# Becca_Sap_Flow_Sensor_MOD3.net
KiCad netlist of a schematic drawn in EAGLE
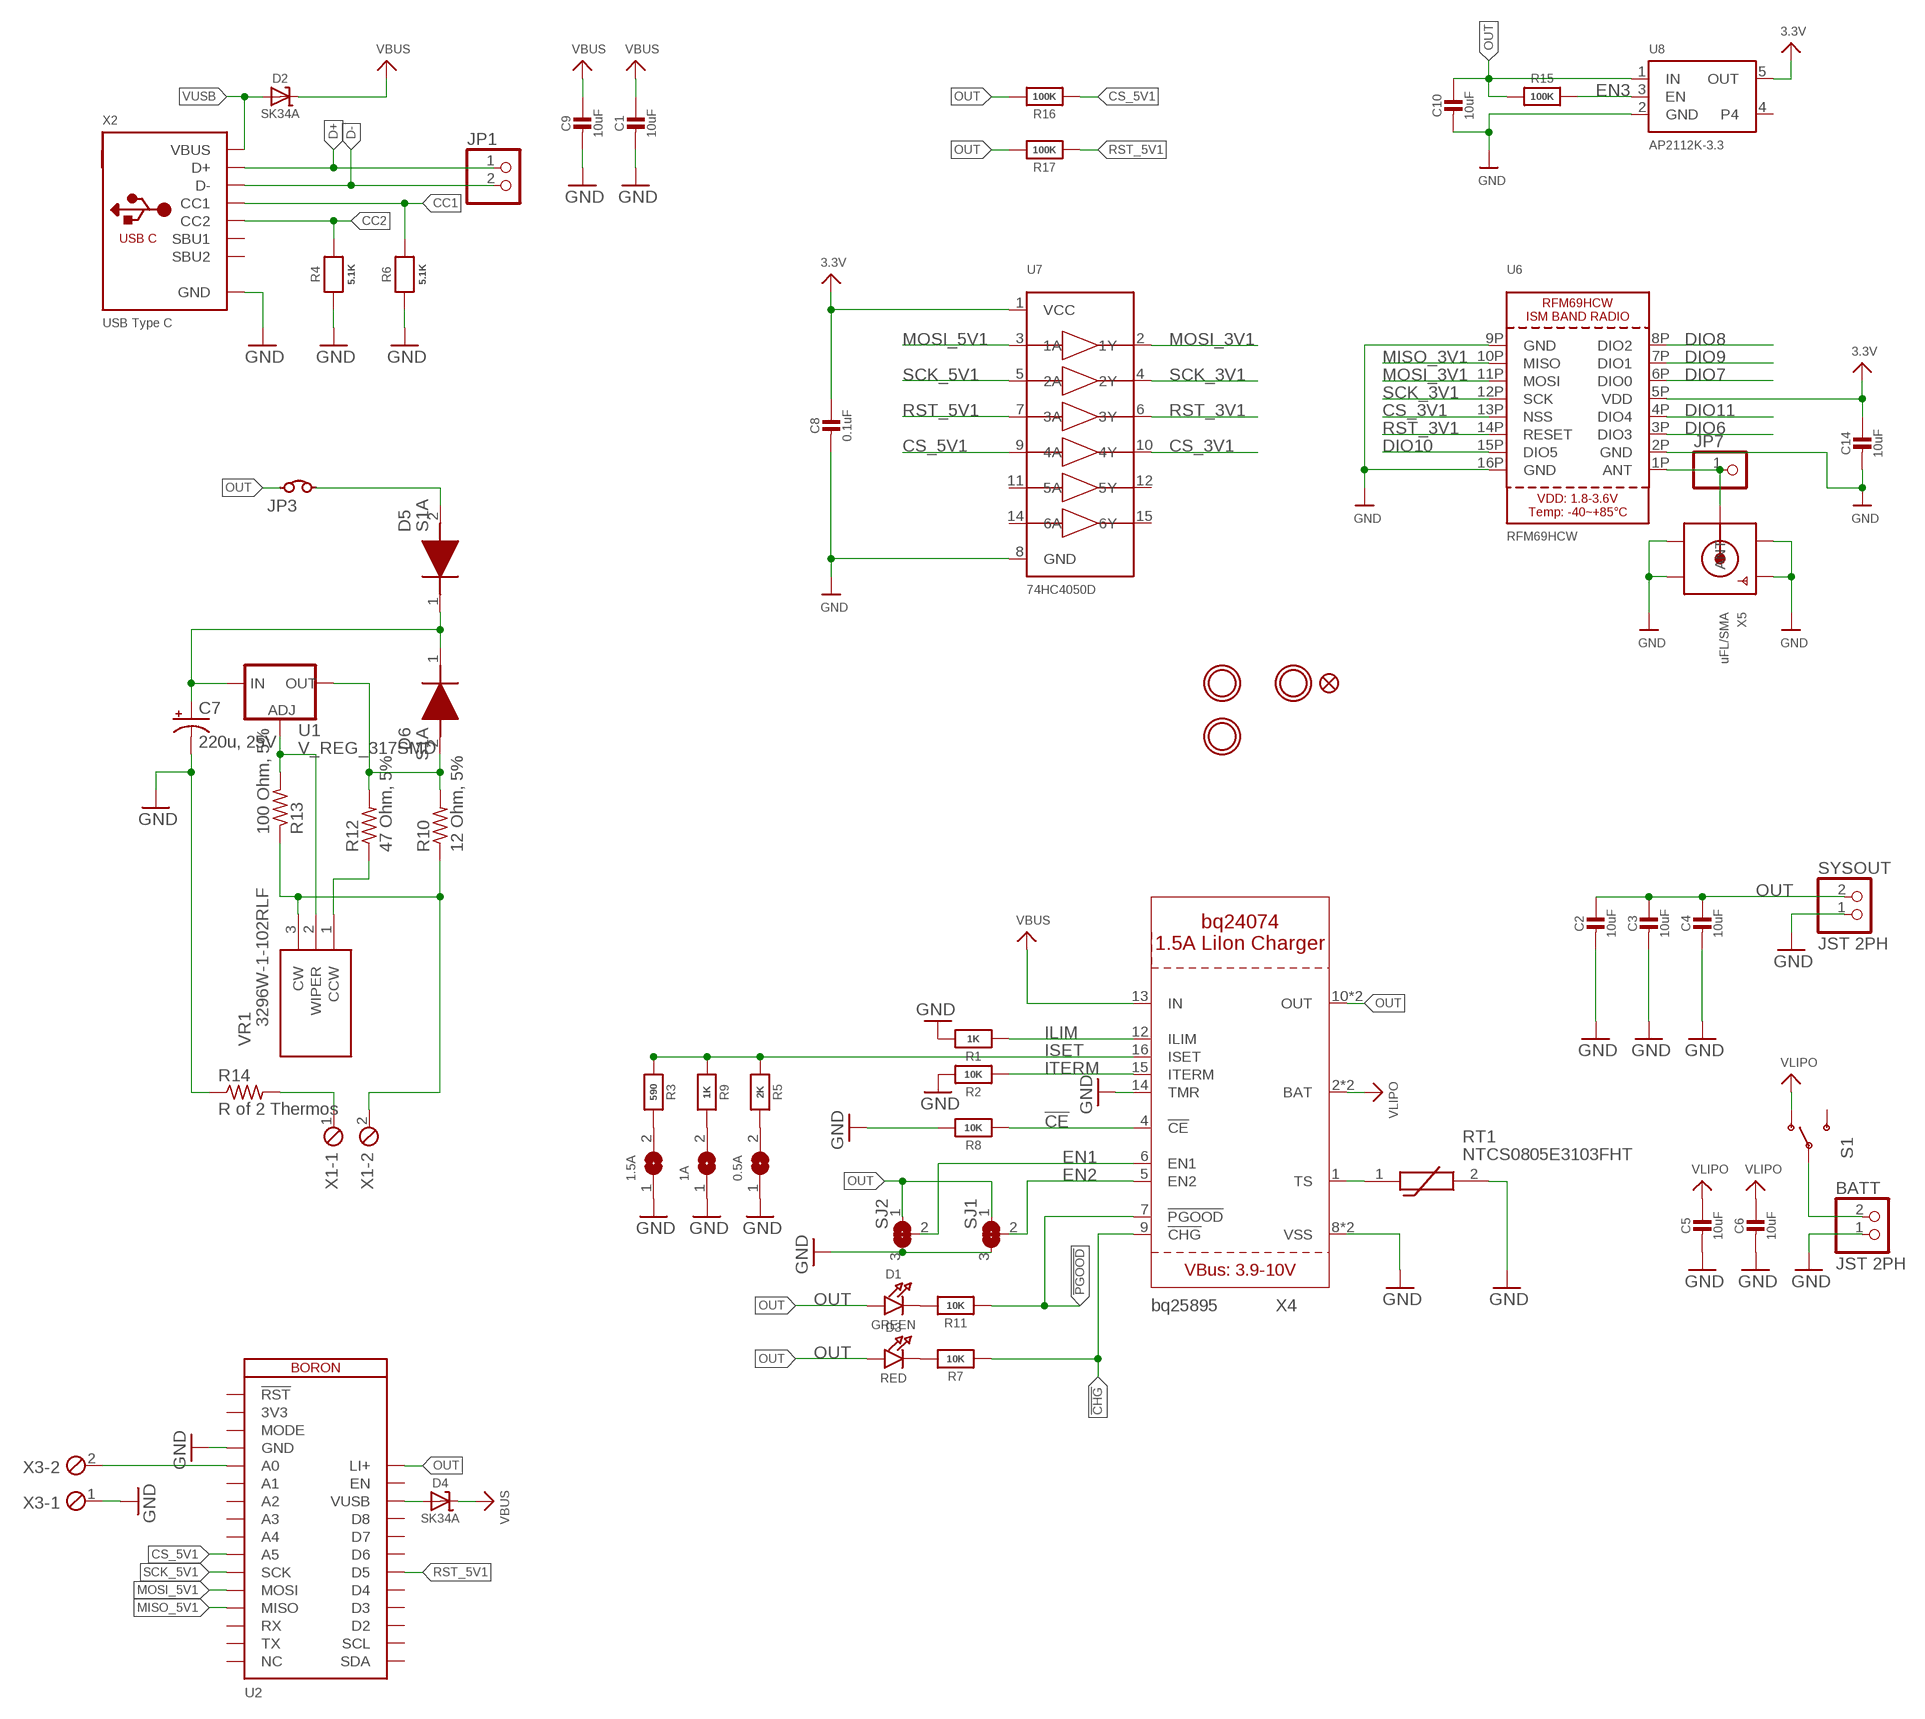
[diagram p0: schematic, sheet 1]

(export (version "E")
  (design (tool "Eeschema 10.0.6"))
  (components
    (comp (ref "0.5A")
      (value "SOLDERJUMPER")
      (footprint "eagle-import:SOLDERJUMPER_ARROW_NOPASTE")
      (libsource (lib "eagle-import") (part "SOLDERJUMPER"))
    )
    (comp (ref "1.5A")
      (value "SOLDERJUMPER")
      (footprint "eagle-import:SOLDERJUMPER_ARROW_NOPASTE")
      (libsource (lib "eagle-import") (part "SOLDERJUMPER"))
    )
    (comp (ref "1A")
      (value "SOLDERJUMPERCLOSED")
      (footprint "eagle-import:SOLDERJUMPER_CLOSEDWIRE")
      (libsource (lib "eagle-import") (part "SOLDERJUMPERCLOSED"))
    )
    (comp (ref "BATT")
      (value "JST 2PH")
      (footprint "eagle-import:JST-PH-2-THM-RA")
      (libsource (lib "eagle-import") (part "JST_2PIN-THM-RA"))
    )
    (comp (ref "C1")
      (value "10uF")
      (footprint "eagle-import:0805-NO")
      (libsource (lib "eagle-import") (part "CAP_CERAMIC0805-NOOUTLINE"))
    )
    (comp (ref "C2")
      (value "10uF")
      (footprint "eagle-import:0805-NO")
      (libsource (lib "eagle-import") (part "CAP_CERAMIC0805-NOOUTLINE"))
    )
    (comp (ref "C3")
      (value "10uF")
      (footprint "eagle-import:0805-NO")
      (libsource (lib "eagle-import") (part "CAP_CERAMIC0805-NOOUTLINE"))
    )
    (comp (ref "C4")
      (value "10uF")
      (footprint "eagle-import:0805-NO")
      (libsource (lib "eagle-import") (part "CAP_CERAMIC0805-NOOUTLINE"))
    )
    (comp (ref "C5")
      (value "10uF")
      (footprint "eagle-import:0805-NO")
      (libsource (lib "eagle-import") (part "CAP_CERAMIC0805-NOOUTLINE"))
    )
    (comp (ref "C6")
      (value "10uF")
      (footprint "eagle-import:0805-NO")
      (libsource (lib "eagle-import") (part "CAP_CERAMIC0805-NOOUTLINE"))
    )
    (comp (ref "C7")
      (value "220u, 25V")
      (footprint "eagle-import:PANASONIC_C")
      (libsource (lib "eagle-import") (part "CPOL-USC"))
    )
    (comp (ref "C8")
      (value "0.1uF")
      (footprint "eagle-import:0805-NO")
      (libsource (lib "eagle-import") (part "CAP_CERAMIC0805-NOOUTLINE"))
    )
    (comp (ref "C9")
      (value "10uF")
      (footprint "eagle-import:0805-NO")
      (libsource (lib "eagle-import") (part "CAP_CERAMIC0805-NOOUTLINE"))
    )
    (comp (ref "C10")
      (value "10uF")
      (footprint "eagle-import:0805-NO")
      (libsource (lib "eagle-import") (part "CAP_CERAMIC0805-NOOUTLINE"))
    )
    (comp (ref "C14")
      (value "10uF")
      (footprint "eagle-import:0805-NO")
      (libsource (lib "eagle-import") (part "CAP_CERAMIC0805-NOOUTLINE"))
    )
    (comp (ref "D1")
      (value "GREEN")
      (footprint "eagle-import:CHIPLED_0603")
      (libsource (lib "eagle-import") (part "LED0603"))
    )
    (comp (ref "D2")
      (value "SK34A")
      (footprint "eagle-import:SMADIODE")
      (libsource (lib "eagle-import") (part "DIODE-SCHOTTKYSMA"))
    )
    (comp (ref "D3")
      (value "RED")
      (footprint "eagle-import:CHIPLED_0603")
      (libsource (lib "eagle-import") (part "LED0603"))
    )
    (comp (ref "D4")
      (value "SK34A")
      (footprint "eagle-import:SMADIODE")
      (libsource (lib "eagle-import") (part "DIODE-SCHOTTKYSMA"))
    )
    (comp (ref "D5")
      (value "S1A")
      (footprint "eagle-import:DIOM5027X250N")
      (fields (field (name "MOUSER_PART_NUMBER") "637-S1A"))
      (libsource (lib "eagle-import") (part "S1A"))
    )
    (comp (ref "D6")
      (value "S1A")
      (footprint "eagle-import:DIOM5027X250N")
      (fields (field (name "MOUSER_PART_NUMBER") "637-S1A"))
      (libsource (lib "eagle-import") (part "S1A"))
    )
    (comp (ref "FID2")
      (value "FIDUCIAL_1MM")
      (footprint "eagle-import:FIDUCIAL_1MM")
      (libsource (lib "eagle-import") (part "FIDUCIAL_1MM"))
    )
    (comp (ref "JP1")
      (value "HEADER-1X2ROUND")
      (footprint "eagle-import:1X02_ROUND")
      (libsource (lib "eagle-import") (part "HEADER-1X2ROUND"))
    )
    (comp (ref "JP3")
      (value "JUMPER")
      (footprint "eagle-import:HDR2X1")
      (libsource (lib "eagle-import") (part "JUMPER"))
    )
    (comp (ref "JP7")
      (value "HEADER-1X1ROUND")
      (footprint "eagle-import:1X01_ROUND")
      (libsource (lib "eagle-import") (part "HEADER-1X1ROUND"))
    )
    (comp (ref "R1")
      (value "1K")
      (footprint "eagle-import:0603-NO")
      (libsource (lib "eagle-import") (part "RESISTOR_0603_NOOUT"))
    )
    (comp (ref "R2")
      (value "10K")
      (footprint "eagle-import:0603-NO")
      (libsource (lib "eagle-import") (part "RESISTOR_0603_NOOUT"))
    )
    (comp (ref "R3")
      (value "590")
      (footprint "eagle-import:0603-NO")
      (libsource (lib "eagle-import") (part "RESISTOR_0603_NOOUT"))
    )
    (comp (ref "R4")
      (value "5.1K")
      (footprint "eagle-import:0603-NO")
      (libsource (lib "eagle-import") (part "RESISTOR_0603_NOOUT"))
    )
    (comp (ref "R5")
      (value "2K")
      (footprint "eagle-import:0603-NO")
      (libsource (lib "eagle-import") (part "RESISTOR_0603_NOOUT"))
    )
    (comp (ref "R6")
      (value "5.1K")
      (footprint "eagle-import:0603-NO")
      (libsource (lib "eagle-import") (part "RESISTOR_0603_NOOUT"))
    )
    (comp (ref "R7")
      (value "10K")
      (footprint "eagle-import:0603-NO")
      (libsource (lib "eagle-import") (part "RESISTOR_0603_NOOUT"))
    )
    (comp (ref "R8")
      (value "10K")
      (footprint "eagle-import:0603-NO")
      (libsource (lib "eagle-import") (part "RESISTOR_0603_NOOUT"))
    )
    (comp (ref "R9")
      (value "1K")
      (footprint "eagle-import:0603-NO")
      (libsource (lib "eagle-import") (part "RESISTOR_0603_NOOUT"))
    )
    (comp (ref "R10")
      (value "12 Ohm, 5%")
      (footprint "eagle-import:R0805")
      (libsource (lib "eagle-import") (part "R-US_R0805"))
    )
    (comp (ref "R11")
      (value "10K")
      (footprint "eagle-import:0603-NO")
      (libsource (lib "eagle-import") (part "RESISTOR_0603_NOOUT"))
    )
    (comp (ref "R12")
      (value "47 Ohm, 5%")
      (footprint "eagle-import:R0805")
      (libsource (lib "eagle-import") (part "R-US_R0805"))
    )
    (comp (ref "R13")
      (value "100 Ohm, 5%")
      (footprint "eagle-import:R0805")
      (libsource (lib "eagle-import") (part "R-US_R0805"))
    )
    (comp (ref "R14")
      (value "R of 2 Thermos")
      (footprint "eagle-import:R0805")
      (libsource (lib "eagle-import") (part "R-US_R0805"))
    )
    (comp (ref "R15")
      (value "100K")
      (footprint "eagle-import:0805-NO")
      (libsource (lib "eagle-import") (part "RESISTOR0805_NOOUTLINE"))
    )
    (comp (ref "R16")
      (value "100K")
      (footprint "eagle-import:0805-NO")
      (libsource (lib "eagle-import") (part "RESISTOR0805_NOOUTLINE"))
    )
    (comp (ref "R17")
      (value "100K")
      (footprint "eagle-import:0805-NO")
      (libsource (lib "eagle-import") (part "RESISTOR0805_NOOUTLINE"))
    )
    (comp (ref "RT1")
      (value "NTCS0805E3103FHT")
      (footprint "eagle-import:THRMC2012X95N")
      (fields (field (name "MOUSER_PART_NUMBER") "594-NTCS0805E3103FHT"))
      (libsource (lib "eagle-import") (part "NTCS0805E3103FHT"))
    )
    (comp (ref "S1")
      (value "SWITCH-SPDTSMD")
      (footprint "eagle-import:SWITCH_SPDT_SMD")
      (libsource (lib "eagle-import") (part "SWITCH-SPDTSMD"))
    )
    (comp (ref "SJ1")
      (value "SOLDERJUMPER_2WAY")
      (footprint "eagle-import:SOLDERJUMPER_2WAY_OPEN_NOPASTE")
      (libsource (lib "eagle-import") (part "SOLDERJUMPER_2WAY"))
    )
    (comp (ref "SJ2")
      (value "SOLDERJUMPER_2WAY")
      (footprint "eagle-import:SOLDERJUMPER_2WAY_OPEN_NOPASTE")
      (libsource (lib "eagle-import") (part "SOLDERJUMPER_2WAY"))
    )
    (comp (ref "SYSOUT")
      (value "JST 2PH")
      (footprint "eagle-import:JST-PH-2-THM-RA")
      (libsource (lib "eagle-import") (part "JST_2PIN-THM-RA"))
    )
    (comp (ref "U$3")
      (value "MOUNTINGHOLE2.5")
      (footprint "eagle-import:MOUNTINGHOLE_2.5_PLATED")
      (libsource (lib "eagle-import") (part "MOUNTINGHOLE2.5"))
    )
    (comp (ref "U$4")
      (value "MOUNTINGHOLE2.5")
      (footprint "eagle-import:MOUNTINGHOLE_2.5_PLATED")
      (libsource (lib "eagle-import") (part "MOUNTINGHOLE2.5"))
    )
    (comp (ref "U$11")
      (value "MOUNTINGHOLE2.5")
      (footprint "eagle-import:MOUNTINGHOLE_2.5_PLATED")
      (libsource (lib "eagle-import") (part "MOUNTINGHOLE2.5"))
    )
    (comp (ref "U1")
      (value "V_REG_317SMD")
      (footprint "eagle-import:SOT223")
      (libsource (lib "eagle-import") (part "V_REG_317SMD"))
    )
    (comp (ref "U2")
      (value "BORON")
      (footprint "eagle-import:BORON")
      (libsource (lib "eagle-import") (part "BORON"))
    )
    (comp (ref "U6")
      (value "RFM69HCW")
      (footprint "eagle-import:RFMHCW_SMT")
      (libsource (lib "eagle-import") (part "RFM69HCW_SMT"))
    )
    (comp (ref "U7")
      (value "74HC4050D")
      (footprint "eagle-import:TSSOP16")
      (libsource (lib "eagle-import") (part "74HC4050DTSSOP"))
    )
    (comp (ref "U8")
      (value "AP2112K-3.3")
      (footprint "eagle-import:SOT23-5")
      (libsource (lib "eagle-import") (part "VREG_SOT23-5"))
    )
    (comp (ref "VR1")
      (value "3296W-1-102RLF")
      (footprint "eagle-import:3296W1102RLF")
      (fields (field (name "MOUSER_PART_NUMBER") "652-3296W-1-102RLF"))
      (libsource (lib "eagle-import") (part "3296W-1-102RLF"))
    )
    (comp (ref "X1")
      (value "MPT2")
      (footprint "eagle-import:2POL254")
      (libsource (lib "eagle-import") (part "MPT2"))
    )
    (comp (ref "X2")
      (value "USB Type C")
      (footprint "eagle-import:USB_C_CUSB31-CFM2AX-01-X")
      (libsource (lib "eagle-import") (part "USB_C"))
    )
    (comp (ref "X3")
      (value "MPT2")
      (footprint "eagle-import:2POL254")
      (libsource (lib "eagle-import") (part "MPT2"))
    )
    (comp (ref "X4")
      (value "BQ24074")
      (footprint "eagle-import:QFN16_3MM")
      (libsource (lib "eagle-import") (part "BQ24074"))
    )
    (comp (ref "X5")
      (value "uFL/SMA")
      (footprint "eagle-import:SMA_EDGELAUNCH_UFL")
      (libsource (lib "eagle-import") (part "SMACONNECTOR_EDGE_UFL"))
    )
  )
  (nets
    (net (code "1") (name "/3V3") (class "Default")
      (node (ref "U2") (pin "2") (pinfunction "3V3_2") (pintype "power_in"))
    )
    (net (code "2") (name "/CS_3V1") (class "Default")
      (node (ref "U6") (pin "13P") (pinfunction "NSS_13P") (pintype "input"))
      (node (ref "U7") (pin "10") (pinfunction "4Y_10") (pintype "bidirectional"))
    )
    (net (code "3") (name "/DIO6") (class "Default")
      (node (ref "U6") (pin "3P") (pinfunction "DIO3_3P") (pintype "bidirectional"))
    )
    (net (code "4") (name "/DIO7") (class "Default")
      (node (ref "U6") (pin "6P") (pinfunction "DIO0_6P") (pintype "bidirectional"))
    )
    (net (code "5") (name "/DIO8") (class "Default")
      (node (ref "U6") (pin "8P") (pinfunction "DIO2_8P") (pintype "bidirectional"))
    )
    (net (code "6") (name "/DIO9") (class "Default")
      (node (ref "U6") (pin "7P") (pinfunction "DIO1_7P") (pintype "bidirectional"))
    )
    (net (code "7") (name "/DIO10") (class "Default")
      (node (ref "U6") (pin "15P") (pinfunction "DIO5_15P") (pintype "bidirectional"))
    )
    (net (code "8") (name "/DIO11") (class "Default")
      (node (ref "U6") (pin "4P") (pinfunction "DIO4_4P") (pintype "bidirectional"))
    )
    (net (code "9") (name "/EN1") (class "Default")
      (node (ref "SJ2") (pin "2") (pinfunction "2_2") (pintype "passive"))
      (node (ref "X4") (pin "6") (pinfunction "EN1_6") (pintype "input"))
    )
    (net (code "10") (name "/EN2") (class "Default")
      (node (ref "SJ1") (pin "2") (pinfunction "2_2") (pintype "passive"))
      (node (ref "X4") (pin "5") (pinfunction "EN2_5") (pintype "input"))
    )
    (net (code "11") (name "/EN3") (class "Default")
      (node (ref "R15") (pin "2") (pinfunction "2_2") (pintype "passive"))
      (node (ref "U8") (pin "3") (pinfunction "EN_3") (pintype "input"))
    )
    (net (code "12") (name "/ILIM") (class "Default")
      (node (ref "R1") (pin "1") (pinfunction "1_1") (pintype "passive"))
      (node (ref "X4") (pin "12") (pinfunction "ILIM_12") (pintype "input"))
    )
    (net (code "13") (name "/ISET") (class "Default")
      (node (ref "R3") (pin "1") (pinfunction "1_1") (pintype "passive"))
      (node (ref "R5") (pin "1") (pinfunction "1_1") (pintype "passive"))
      (node (ref "R9") (pin "1") (pinfunction "1_1") (pintype "passive"))
      (node (ref "X4") (pin "16") (pinfunction "ISET_16") (pintype "input"))
    )
    (net (code "14") (name "/ITERM") (class "Default")
      (node (ref "R2") (pin "1") (pinfunction "1_1") (pintype "passive"))
      (node (ref "X4") (pin "15") (pinfunction "ITERM_15") (pintype "input"))
    )
    (net (code "15") (name "/MISO_3V1") (class "Default")
      (node (ref "U6") (pin "10P") (pinfunction "MISO_10P") (pintype "output"))
    )
    (net (code "16") (name "/MOSI_3V1") (class "Default")
      (node (ref "U6") (pin "11P") (pinfunction "MOSI_11P") (pintype "input"))
      (node (ref "U7") (pin "2") (pinfunction "1Y_2") (pintype "bidirectional"))
    )
    (net (code "17") (name "/RST_3V1") (class "Default")
      (node (ref "U6") (pin "14P") (pinfunction "RESET_14P") (pintype "input"))
      (node (ref "U7") (pin "6") (pinfunction "3Y_6") (pintype "bidirectional"))
    )
    (net (code "18") (name "/SCK_3V1") (class "Default")
      (node (ref "U6") (pin "12P") (pinfunction "SCK_12P") (pintype "input"))
      (node (ref "U7") (pin "4") (pinfunction "2Y_4") (pintype "bidirectional"))
    )
    (net (code "19") (name "/~{CE}") (class "Default")
      (node (ref "R8") (pin "1") (pinfunction "1_1") (pintype "passive"))
      (node (ref "X4") (pin "4") (pinfunction "~{CE}_4") (pintype "input"))
    )
    (net (code "20") (name "/~{CHG}") (class "Default")
      (node (ref "R7") (pin "1") (pinfunction "1_1") (pintype "passive"))
      (node (ref "X4") (pin "9") (pinfunction "~{CHG}_9") (pintype "output"))
    )
    (net (code "21") (name "/~{PGOOD}") (class "Default")
      (node (ref "R11") (pin "1") (pinfunction "1_1") (pintype "passive"))
      (node (ref "X4") (pin "7") (pinfunction "~{PGOOD}_7") (pintype "output"))
    )
    (net (code "22") (name "3.3V") (class "Default")
      (node (ref "C14") (pin "1") (pinfunction "1_1") (pintype "passive"))
      (node (ref "C8") (pin "1") (pinfunction "1_1") (pintype "passive"))
      (node (ref "U6") (pin "5P") (pinfunction "VDD_5P") (pintype "power_in"))
      (node (ref "U7") (pin "1") (pinfunction "VCC_1") (pintype "bidirectional"))
      (node (ref "U8") (pin "5") (pinfunction "OUT_5") (pintype "power_in"))
    )
    (net (code "23") (name "CC1") (class "Default")
      (node (ref "R6") (pin "2") (pinfunction "2_2") (pintype "passive"))
      (node (ref "X2") (pin "A5") (pinfunction "CC1_A5") (pintype "bidirectional"))
    )
    (net (code "24") (name "CC2") (class "Default")
      (node (ref "R4") (pin "2") (pinfunction "2_2") (pintype "passive"))
      (node (ref "X2") (pin "B5") (pinfunction "CC2_B5") (pintype "bidirectional"))
    )
    (net (code "25") (name "CS_5V1") (class "Default")
      (node (ref "R16") (pin "1") (pinfunction "1_1") (pintype "passive"))
      (node (ref "U2") (pin "10") (pinfunction "A5_10") (pintype "bidirectional"))
      (node (ref "U7") (pin "9") (pinfunction "4A_9") (pintype "bidirectional"))
    )
    (net (code "26") (name "D+") (class "Default")
      (node (ref "JP1") (pin "1") (pinfunction "1_1") (pintype "passive"))
      (node (ref "X2") (pin "A6") (pinfunction "D+_A6") (pintype "bidirectional"))
      (node (ref "X2") (pin "B6") (pinfunction "D+_B6") (pintype "bidirectional"))
    )
    (net (code "27") (name "D-") (class "Default")
      (node (ref "JP1") (pin "2") (pinfunction "2_2") (pintype "passive"))
      (node (ref "X2") (pin "A7") (pinfunction "D-_A7") (pintype "bidirectional"))
      (node (ref "X2") (pin "B7") (pinfunction "D-_B7") (pintype "bidirectional"))
    )
    (net (code "28") (name "GND") (class "Default")
      (node (ref "0.5A") (pin "1") (pinfunction "1_1") (pintype "passive"))
      (node (ref "1.5A") (pin "1") (pinfunction "1_1") (pintype "passive"))
      (node (ref "1A") (pin "1") (pinfunction "1_1") (pintype "passive"))
      (node (ref "BATT") (pin "1") (pinfunction "2_1") (pintype "passive"))
      (node (ref "C1") (pin "2") (pinfunction "2_2") (pintype "passive"))
      (node (ref "C10") (pin "2") (pinfunction "2_2") (pintype "passive"))
      (node (ref "C14") (pin "2") (pinfunction "2_2") (pintype "passive"))
      (node (ref "C2") (pin "2") (pinfunction "2_2") (pintype "passive"))
      (node (ref "C3") (pin "2") (pinfunction "2_2") (pintype "passive"))
      (node (ref "C4") (pin "2") (pinfunction "2_2") (pintype "passive"))
      (node (ref "C5") (pin "2") (pinfunction "2_2") (pintype "passive"))
      (node (ref "C6") (pin "2") (pinfunction "2_2") (pintype "passive"))
      (node (ref "C7") (pin "-") (pinfunction "-_-") (pintype "passive"))
      (node (ref "C8") (pin "2") (pinfunction "2_2") (pintype "passive"))
      (node (ref "C9") (pin "2") (pinfunction "2_2") (pintype "passive"))
      (node (ref "R1") (pin "2") (pinfunction "2_2") (pintype "passive"))
      (node (ref "R14") (pin "1") (pinfunction "1_1") (pintype "passive"))
      (node (ref "R2") (pin "2") (pinfunction "2_2") (pintype "passive"))
      (node (ref "R4") (pin "1") (pinfunction "1_1") (pintype "passive"))
      (node (ref "R6") (pin "1") (pinfunction "1_1") (pintype "passive"))
      (node (ref "R8") (pin "2") (pinfunction "2_2") (pintype "passive"))
      (node (ref "RT1") (pin "2") (pinfunction "2_2") (pintype "bidirectional"))
      (node (ref "SJ1") (pin "3") (pinfunction "3_3") (pintype "passive"))
      (node (ref "SJ2") (pin "3") (pinfunction "3_3") (pintype "passive"))
      (node (ref "SYSOUT") (pin "1") (pinfunction "2_1") (pintype "passive"))
      (node (ref "U2") (pin "4") (pinfunction "GND_4") (pintype "power_in"))
      (node (ref "U6") (pin "16P") (pinfunction "GND_16P") (pintype "power_in"))
      (node (ref "U6") (pin "2P") (pinfunction "GND_2P") (pintype "power_in"))
      (node (ref "U6") (pin "9P") (pinfunction "GND_9P") (pintype "power_in"))
      (node (ref "U7") (pin "8") (pinfunction "GND_8") (pintype "bidirectional"))
      (node (ref "U8") (pin "2") (pinfunction "GND_2") (pintype "power_in"))
      (node (ref "X2") (pin "A1B12") (pinfunction "GND_A1B12") (pintype "power_in"))
      (node (ref "X2") (pin "B1A12") (pinfunction "GND_B1A12") (pintype "power_in"))
      (node (ref "X3") (pin "1") (pinfunction "1_1") (pintype "passive"))
      (node (ref "X4") (pin "14") (pinfunction "TMR_14") (pintype "input"))
      (node (ref "X4") (pin "8") (pinfunction "VSS_8") (pintype "power_in"))
      (node (ref "X4") (pin "THERMAL") (pinfunction "VSS_THERMAL") (pintype "power_in"))
      (node (ref "X5") (pin "GND@1") (pinfunction "GND1_GND@1") (pintype "power_in"))
      (node (ref "X5") (pin "GND@2") (pinfunction "GND2_GND@2") (pintype "power_in"))
      (node (ref "X5") (pin "GND@3") (pinfunction "GND3_GND@3") (pintype "power_in"))
      (node (ref "X5") (pin "GND@4") (pinfunction "GND4_GND@4") (pintype "power_in"))
    )
    (net (code "29") (name "MISO_5V1") (class "Default")
      (node (ref "U2") (pin "13") (pinfunction "MISO_13") (pintype "bidirectional"))
    )
    (net (code "30") (name "MOSI_5V1") (class "Default")
      (node (ref "U2") (pin "12") (pinfunction "MOSI_12") (pintype "bidirectional"))
      (node (ref "U7") (pin "3") (pinfunction "1A_3") (pintype "bidirectional"))
    )
    (net (code "31") (name "Net-(0.5A-Pad2)") (class "Default")
      (node (ref "0.5A") (pin "2") (pinfunction "2_2") (pintype "passive"))
      (node (ref "R5") (pin "2") (pinfunction "2_2") (pintype "passive"))
    )
    (net (code "32") (name "Net-(1.5A-Pad2)") (class "Default")
      (node (ref "1.5A") (pin "2") (pinfunction "2_2") (pintype "passive"))
      (node (ref "R3") (pin "2") (pinfunction "2_2") (pintype "passive"))
    )
    (net (code "33") (name "Net-(1A-Pad2)") (class "Default")
      (node (ref "1A") (pin "2") (pinfunction "2_2") (pintype "passive"))
      (node (ref "R9") (pin "2") (pinfunction "2_2") (pintype "passive"))
    )
    (net (code "34") (name "Net-(BATT-1)") (class "Default")
      (node (ref "BATT") (pin "2") (pinfunction "1_2") (pintype "passive"))
      (node (ref "S1") (pin "2") (pinfunction "P_2") (pintype "passive"))
    )
    (net (code "35") (name "Net-(D1-PadC)") (class "Default")
      (node (ref "D1") (pin "C") (pinfunction "C_C") (pintype "passive"))
      (node (ref "R11") (pin "2") (pinfunction "2_2") (pintype "passive"))
    )
    (net (code "36") (name "Net-(D3-PadC)") (class "Default")
      (node (ref "D3") (pin "C") (pinfunction "C_C") (pintype "passive"))
      (node (ref "R7") (pin "2") (pinfunction "2_2") (pintype "passive"))
    )
    (net (code "37") (name "Net-(D5-A)") (class "Default")
      (node (ref "D5") (pin "2") (pinfunction "A_2") (pintype "bidirectional"))
      (node (ref "JP3") (pin "2") (pinfunction "2_2") (pintype "passive"))
    )
    (net (code "38") (name "Net-(D5-K)") (class "Default")
      (node (ref "C7") (pin "+") (pinfunction "+_+") (pintype "passive"))
      (node (ref "D5") (pin "1") (pinfunction "K_1") (pintype "bidirectional"))
      (node (ref "D6") (pin "1") (pinfunction "K_1") (pintype "bidirectional"))
      (node (ref "U1") (pin "3") (pinfunction "IN_3") (pintype "input"))
    )
    (net (code "39") (name "Net-(D6-A)") (class "Default")
      (node (ref "D6") (pin "2") (pinfunction "A_2") (pintype "bidirectional"))
      (node (ref "R10") (pin "2") (pinfunction "2_2") (pintype "passive"))
      (node (ref "R12") (pin "2") (pinfunction "2_2") (pintype "passive"))
      (node (ref "U1") (pin "2") (pinfunction "OUT_2") (pintype "output"))
    )
    (net (code "40") (name "Net-(R14-Pad2)") (class "Default")
      (node (ref "R14") (pin "2") (pinfunction "2_2") (pintype "passive"))
      (node (ref "X1") (pin "1") (pinfunction "1_1") (pintype "passive"))
    )
    (net (code "41") (name "Net-(U1-ADJ)") (class "Default")
      (node (ref "R13") (pin "2") (pinfunction "2_2") (pintype "passive"))
      (node (ref "U1") (pin "1") (pinfunction "ADJ_1") (pintype "input"))
      (node (ref "VR1") (pin "2") (pinfunction "WIPER_2") (pintype "bidirectional"))
    )
    (net (code "42") (name "Net-(U2-A0)") (class "Default")
      (node (ref "U2") (pin "5") (pinfunction "A0_5") (pintype "bidirectional"))
      (node (ref "X3") (pin "2") (pinfunction "1_2") (pintype "passive"))
    )
    (net (code "43") (name "Net-(U2-VUSB)") (class "Default")
      (node (ref "D4") (pin "A") (pinfunction "A_A") (pintype "passive"))
      (node (ref "U2") (pin "26") (pinfunction "VUSB_26") (pintype "power_in"))
    )
    (net (code "44") (name "Net-(U6-ANT)") (class "Default")
      (node (ref "JP7") (pin "1") (pinfunction "1_1") (pintype "passive"))
      (node (ref "U6") (pin "1P") (pinfunction "ANT_1P") (pintype "bidirectional"))
      (node (ref "X5") (pin "P") (pinfunction "ANT_P") (pintype "bidirectional"))
    )
    (net (code "45") (name "Net-(VR1-CCW)") (class "Default")
      (node (ref "R12") (pin "1") (pinfunction "1_1") (pintype "passive"))
      (node (ref "VR1") (pin "1") (pinfunction "CCW_1") (pintype "bidirectional"))
    )
    (net (code "46") (name "Net-(VR1-CW)") (class "Default")
      (node (ref "R10") (pin "1") (pinfunction "1_1") (pintype "passive"))
      (node (ref "R13") (pin "1") (pinfunction "1_1") (pintype "passive"))
      (node (ref "VR1") (pin "3") (pinfunction "CW_3") (pintype "bidirectional"))
      (node (ref "X1") (pin "2") (pinfunction "1_2") (pintype "passive"))
    )
    (net (code "47") (name "Net-(X4-TS)") (class "Default")
      (node (ref "RT1") (pin "1") (pinfunction "1_1") (pintype "bidirectional"))
      (node (ref "X4") (pin "1") (pinfunction "TS_1") (pintype "input"))
    )
    (net (code "48") (name "OUT") (class "Default")
      (node (ref "C10") (pin "1") (pinfunction "1_1") (pintype "passive"))
      (node (ref "C2") (pin "1") (pinfunction "1_1") (pintype "passive"))
      (node (ref "C3") (pin "1") (pinfunction "1_1") (pintype "passive"))
      (node (ref "C4") (pin "1") (pinfunction "1_1") (pintype "passive"))
      (node (ref "D1") (pin "A") (pinfunction "A_A") (pintype "passive"))
      (node (ref "D3") (pin "A") (pinfunction "A_A") (pintype "passive"))
      (node (ref "JP3") (pin "1") (pinfunction "1_1") (pintype "passive"))
      (node (ref "R15") (pin "1") (pinfunction "1_1") (pintype "passive"))
      (node (ref "R16") (pin "2") (pinfunction "2_2") (pintype "passive"))
      (node (ref "R17") (pin "2") (pinfunction "2_2") (pintype "passive"))
      (node (ref "SJ1") (pin "1") (pinfunction "1_1") (pintype "passive"))
      (node (ref "SJ2") (pin "1") (pinfunction "1_1") (pintype "passive"))
      (node (ref "SYSOUT") (pin "2") (pinfunction "1_2") (pintype "passive"))
      (node (ref "U2") (pin "28") (pinfunction "LI+_28") (pintype "power_in"))
      (node (ref "U8") (pin "1") (pinfunction "IN_1") (pintype "power_in"))
      (node (ref "X4") (pin "10") (pinfunction "OUT_10") (pintype "output"))
      (node (ref "X4") (pin "11") (pinfunction "OUT_11") (pintype "output"))
    )
    (net (code "49") (name "RST_5V1") (class "Default")
      (node (ref "R17") (pin "1") (pinfunction "1_1") (pintype "passive"))
      (node (ref "U2") (pin "22") (pinfunction "D5_22") (pintype "bidirectional"))
      (node (ref "U7") (pin "7") (pinfunction "3A_7") (pintype "bidirectional"))
    )
    (net (code "50") (name "SCK_5V1") (class "Default")
      (node (ref "U2") (pin "11") (pinfunction "SCK_11") (pintype "bidirectional"))
      (node (ref "U7") (pin "5") (pinfunction "2A_5") (pintype "bidirectional"))
    )
    (net (code "51") (name "VBUS") (class "Default")
      (node (ref "C1") (pin "1") (pinfunction "1_1") (pintype "passive"))
      (node (ref "C9") (pin "1") (pinfunction "1_1") (pintype "passive"))
      (node (ref "D2") (pin "C") (pinfunction "C_C") (pintype "passive"))
      (node (ref "D4") (pin "C") (pinfunction "C_C") (pintype "passive"))
      (node (ref "X4") (pin "13") (pinfunction "IN_13") (pintype "power_in"))
    )
    (net (code "52") (name "VLIPO") (class "Default")
      (node (ref "C5") (pin "1") (pinfunction "1_1") (pintype "passive"))
      (node (ref "C6") (pin "1") (pinfunction "1_1") (pintype "passive"))
      (node (ref "S1") (pin "1") (pinfunction "O_1") (pintype "passive"))
      (node (ref "X4") (pin "2") (pinfunction "BAT_2") (pintype "input"))
      (node (ref "X4") (pin "3") (pinfunction "BAT_3") (pintype "input"))
    )
    (net (code "53") (name "VUSB") (class "Default")
      (node (ref "D2") (pin "A") (pinfunction "A_A") (pintype "passive"))
      (node (ref "X2") (pin "A4B9") (pinfunction "VBUS_A4B9") (pintype "power_in"))
      (node (ref "X2") (pin "B4A9") (pinfunction "VBUS_B4A9") (pintype "power_in"))
    )
    (net (code "54") (name "unconnected-(S1-S-Pad3)") (class "Default")
      (node (ref "S1") (pin "3") (pinfunction "S_3") (pintype "passive"))
    )
    (net (code "55") (name "unconnected-(U2-A1-Pad6)") (class "Default")
      (node (ref "U2") (pin "6") (pinfunction "A1_6") (pintype "bidirectional"))
    )
    (net (code "56") (name "unconnected-(U2-A2-Pad7)") (class "Default")
      (node (ref "U2") (pin "7") (pinfunction "A2_7") (pintype "bidirectional"))
    )
    (net (code "57") (name "unconnected-(U2-A3-Pad8)") (class "Default")
      (node (ref "U2") (pin "8") (pinfunction "A3_8") (pintype "bidirectional"))
    )
    (net (code "58") (name "unconnected-(U2-A4-Pad9)") (class "Default")
      (node (ref "U2") (pin "9") (pinfunction "A4_9") (pintype "bidirectional"))
    )
    (net (code "59") (name "unconnected-(U2-D2-Pad19)") (class "Default")
      (node (ref "U2") (pin "19") (pinfunction "D2_19") (pintype "bidirectional"))
    )
    (net (code "60") (name "unconnected-(U2-D3-Pad20)") (class "Default")
      (node (ref "U2") (pin "20") (pinfunction "D3_20") (pintype "bidirectional"))
    )
    (net (code "61") (name "unconnected-(U2-D4-Pad21)") (class "Default")
      (node (ref "U2") (pin "21") (pinfunction "D4_21") (pintype "bidirectional"))
    )
    (net (code "62") (name "unconnected-(U2-D6-Pad23)") (class "Default")
      (node (ref "U2") (pin "23") (pinfunction "D6_23") (pintype "bidirectional"))
    )
    (net (code "63") (name "unconnected-(U2-D7-Pad24)") (class "Default")
      (node (ref "U2") (pin "24") (pinfunction "D7_24") (pintype "bidirectional"))
    )
    (net (code "64") (name "unconnected-(U2-D8-Pad25)") (class "Default")
      (node (ref "U2") (pin "25") (pinfunction "D8_25") (pintype "bidirectional"))
    )
    (net (code "65") (name "unconnected-(U2-EN-Pad27)") (class "Default")
      (node (ref "U2") (pin "27") (pinfunction "EN_27") (pintype "input"))
    )
    (net (code "66") (name "unconnected-(U2-MODE-Pad3)") (class "Default")
      (node (ref "U2") (pin "3") (pinfunction "MODE_3") (pintype "bidirectional"))
    )
    (net (code "67") (name "unconnected-(U2-NC-Pad16)") (class "Default")
      (node (ref "U2") (pin "16") (pinfunction "NC_16") (pintype "bidirectional"))
    )
    (net (code "68") (name "unconnected-(U2-RX-Pad14)") (class "Default")
      (node (ref "U2") (pin "14") (pinfunction "RX_14") (pintype "bidirectional"))
    )
    (net (code "69") (name "unconnected-(U2-SCL-Pad18)") (class "Default")
      (node (ref "U2") (pin "18") (pinfunction "SCL_18") (pintype "bidirectional"))
    )
    (net (code "70") (name "unconnected-(U2-SDA-Pad17)") (class "Default")
      (node (ref "U2") (pin "17") (pinfunction "SDA_17") (pintype "bidirectional"))
    )
    (net (code "71") (name "unconnected-(U2-TX-Pad15)") (class "Default")
      (node (ref "U2") (pin "15") (pinfunction "TX_15") (pintype "bidirectional"))
    )
    (net (code "72") (name "unconnected-(U2-~{RST}-Pad1)") (class "Default")
      (node (ref "U2") (pin "1") (pinfunction "~{RST}_1") (pintype "input"))
    )
    (net (code "73") (name "unconnected-(U7-5A-Pad11)") (class "Default")
      (node (ref "U7") (pin "11") (pinfunction "5A_11") (pintype "bidirectional"))
    )
    (net (code "74") (name "unconnected-(U7-5Y-Pad12)") (class "Default")
      (node (ref "U7") (pin "12") (pinfunction "5Y_12") (pintype "bidirectional"))
    )
    (net (code "75") (name "unconnected-(U7-6A-Pad14)") (class "Default")
      (node (ref "U7") (pin "14") (pinfunction "6A_14") (pintype "bidirectional"))
    )
    (net (code "76") (name "unconnected-(U7-6Y-Pad15)") (class "Default")
      (node (ref "U7") (pin "15") (pinfunction "6Y_15") (pintype "bidirectional"))
    )
    (net (code "77") (name "unconnected-(U8-P4-Pad4)") (class "Default")
      (node (ref "U8") (pin "4") (pinfunction "P4_4") (pintype "bidirectional"))
    )
    (net (code "78") (name "unconnected-(X2-SBU1-PadA8)") (class "Default")
      (node (ref "X2") (pin "A8") (pinfunction "SBU1_A8") (pintype "bidirectional"))
    )
    (net (code "79") (name "unconnected-(X2-SBU2-PadB8)") (class "Default")
      (node (ref "X2") (pin "B8") (pinfunction "SBU2_B8") (pintype "bidirectional"))
    )
  )
)
